# RGB-Controller.net
KiCad netlist of a schematic drawn in EasyEDA
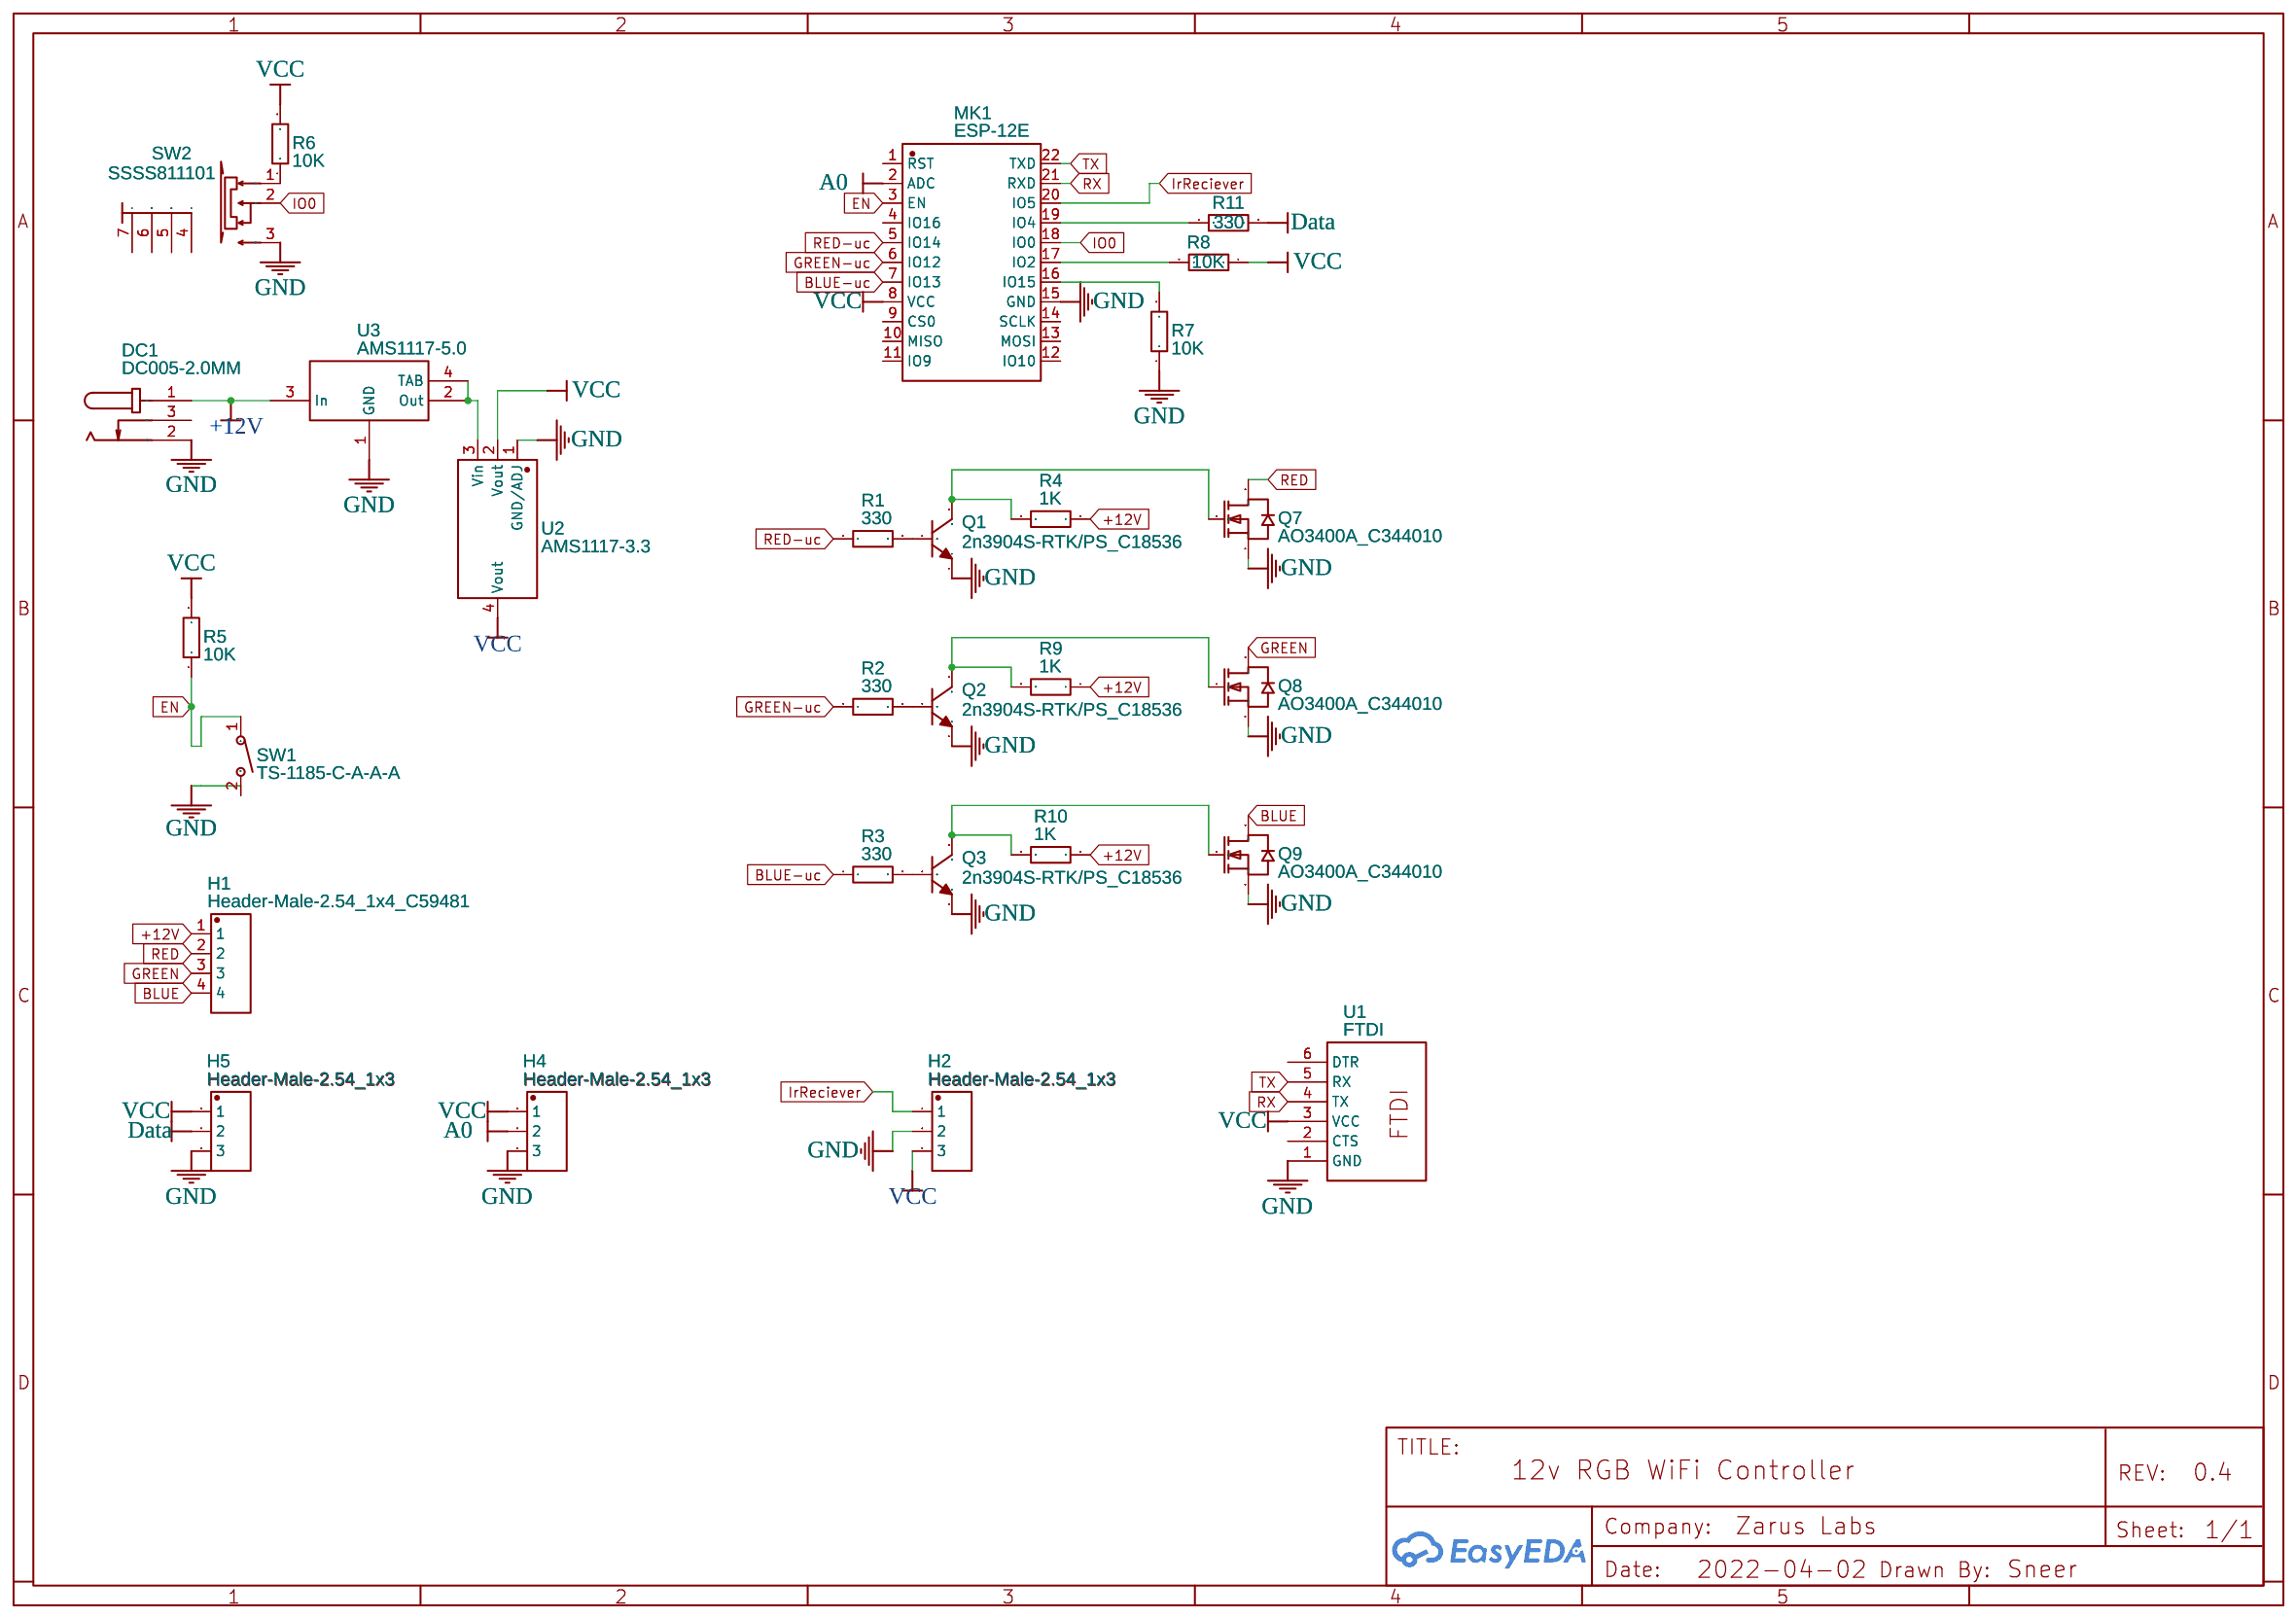
[diagram p0: schematic sheet]

(export (version "E")
  (design (tool "Eeschema 10.0.6"))
  (components
    (comp (ref "DC1")
      (value "DC005-2.0MM")
      (fields (field (name "BOM_Supplier Part") "C111567"))
      (libsource (lib "") (part "DC005-2.0MM"))
    )
    (comp (ref "H1")
      (value "Header-Male-2.54_1x4_C59481")
      (fields
        (field (name "BOM_Manufacturer Part") "Headers  Pins 1*4P")
        (field (name "BOM_Supplier Part") "C59481")
      )
      (libsource (lib "") (part "Header-Male-2.54_1x4_C59481"))
    )
    (comp (ref "H2") (value "Header-Male-2.54_1x3") (libsource (lib "") (part "Header-Male-2.54_1x3")))
    (comp (ref "H4") (value "Header-Male-2.54_1x3") (libsource (lib "") (part "Header-Male-2.54_1x3")))
    (comp (ref "H5") (value "Header-Male-2.54_1x3") (libsource (lib "") (part "Header-Male-2.54_1x3")))
    (comp (ref "MK1")
      (value "ESP-12E")
      (fields (field (name "BOM_Supplier Part") "C89297"))
      (libsource (lib "") (part "ESP-12E"))
    )
    (comp (ref "Q1")
      (value "2n3904S-RTK/PS_C18536")
      (fields
        (field (name "BOM_Manufacturer Part") "2n3904S-RTK/PS")
        (field (name "BOM_Supplier Part") "C18536")
      )
      (libsource (lib "") (part "2n3904S-RTK/PS_C18536"))
    )
    (comp (ref "Q2")
      (value "2n3904S-RTK/PS_C18536")
      (fields
        (field (name "BOM_Manufacturer Part") "2n3904S-RTK/PS")
        (field (name "BOM_Supplier Part") "C18536")
      )
      (libsource (lib "") (part "2n3904S-RTK/PS_C18536"))
    )
    (comp (ref "Q3")
      (value "2n3904S-RTK/PS_C18536")
      (fields
        (field (name "BOM_Manufacturer Part") "2n3904S-RTK/PS")
        (field (name "BOM_Supplier Part") "C18536")
      )
      (libsource (lib "") (part "2n3904S-RTK/PS_C18536"))
    )
    (comp (ref "Q7")
      (value "AO3400A_C344010")
      (fields (field (name "BOM_Manufacturer Part") "AO3400A") (field (name "BOM_Supplier Part") "C344010"))
      (libsource (lib "") (part "AO3400A_C344010"))
    )
    (comp (ref "Q8")
      (value "AO3400A_C344010")
      (fields (field (name "BOM_Manufacturer Part") "AO3400A") (field (name "BOM_Supplier Part") "C344010"))
      (libsource (lib "") (part "AO3400A_C344010"))
    )
    (comp (ref "Q9")
      (value "AO3400A_C344010")
      (fields (field (name "BOM_Manufacturer Part") "AO3400A") (field (name "BOM_Supplier Part") "C344010"))
      (libsource (lib "") (part "AO3400A_C344010"))
    )
    (comp (ref "R1")
      (value "330")
      (fields
        (field (name "BOM_Manufacturer Part") "0805W8J0331T5E")
        (field (name "BOM_Supplier Part") "C25306")
      )
      (libsource (lib "") (part "0805W8J0331T5E"))
    )
    (comp (ref "R2")
      (value "330")
      (fields
        (field (name "BOM_Manufacturer Part") "0805W8J0331T5E")
        (field (name "BOM_Supplier Part") "C25306")
      )
      (libsource (lib "") (part "0805W8J0331T5E"))
    )
    (comp (ref "R3")
      (value "330")
      (fields
        (field (name "BOM_Manufacturer Part") "0805W8J0331T5E")
        (field (name "BOM_Supplier Part") "C25306")
      )
      (libsource (lib "") (part "0805W8J0331T5E"))
    )
    (comp (ref "R4")
      (value "1K")
      (fields
        (field (name "BOM_Manufacturer Part") "1210W3J0102T5E")
        (field (name "BOM_Supplier Part") "C25681")
      )
      (libsource (lib "") (part "1210W3J0102T5E"))
    )
    (comp (ref "R5")
      (value "10K")
      (fields
        (field (name "BOM_Manufacturer Part") "1206W4F1002T5E")
        (field (name "BOM_Supplier Part") "C17902")
      )
      (libsource (lib "") (part "1206W4F1002T5E"))
    )
    (comp (ref "R6")
      (value "10K")
      (fields
        (field (name "BOM_Manufacturer Part") "1206W4F1002T5E")
        (field (name "BOM_Supplier Part") "C17902")
      )
      (libsource (lib "") (part "1206W4F1002T5E"))
    )
    (comp (ref "R7")
      (value "10K")
      (fields
        (field (name "BOM_Manufacturer Part") "1206W4F1002T5E")
        (field (name "BOM_Supplier Part") "C17902")
      )
      (libsource (lib "") (part "1206W4F1002T5E"))
    )
    (comp (ref "R8")
      (value "10K")
      (fields
        (field (name "BOM_Manufacturer Part") "1206W4F1002T5E")
        (field (name "BOM_Supplier Part") "C17902")
      )
      (libsource (lib "") (part "1206W4F1002T5E_1"))
    )
    (comp (ref "R9")
      (value "1K")
      (fields
        (field (name "BOM_Manufacturer Part") "1210W3J0102T5E")
        (field (name "BOM_Supplier Part") "C25681")
      )
      (libsource (lib "") (part "1210W3J0102T5E"))
    )
    (comp (ref "R10")
      (value "1K")
      (fields
        (field (name "BOM_Manufacturer Part") "1210W3J0102T5E")
        (field (name "BOM_Supplier Part") "C25681")
      )
      (libsource (lib "") (part "1210W3J0102T5E"))
    )
    (comp (ref "R11")
      (value "330")
      (fields
        (field (name "BOM_Manufacturer Part") "0805W8J0331T5E")
        (field (name "BOM_Supplier Part") "C25306")
      )
      (libsource (lib "") (part "0805W8J0331T5E"))
    )
    (comp (ref "SW1")
      (value "TS-1185-C-A-A-A")
      (fields (field (name "BOM_Supplier Part") "C561518"))
      (libsource (lib "") (part "TS-1185-C-A-A-A"))
    )
    (comp (ref "SW2")
      (value "SSSS811101")
      (fields (field (name "BOM_Supplier Part") "C109335"))
      (libsource (lib "") (part "SSSS811101"))
    )
    (comp (ref "U1") (value "FTDI") (libsource (lib "") (part "FTDI")))
    (comp (ref "U2")
      (value "AMS1117-3.3")
      (fields (field (name "BOM_Supplier Part") "C6186"))
      (libsource (lib "") (part "AMS1117-3.3"))
    )
    (comp (ref "U3")
      (value "AMS1117-5.0")
      (fields (field (name "BOM_Supplier Part") "C6187"))
      (libsource (lib "") (part "AMS1117-5.0"))
    )
  )
  (nets
    (net (code "1") (name "+12V") (class "Default")
      (node (ref "DC1") (pin "1") (pinfunction "1_1") (pintype "unspecified"))
      (node (ref "H1") (pin "1") (pinfunction "1_1") (pintype "unspecified"))
      (node (ref "R10") (pin "1") (pinfunction "1_1") (pintype "input"))
      (node (ref "R4") (pin "1") (pinfunction "1_1") (pintype "input"))
      (node (ref "R9") (pin "1") (pinfunction "1_1") (pintype "input"))
      (node (ref "U3") (pin "3") (pinfunction "In_3") (pintype "unspecified"))
    )
    (net (code "2") (name "A0") (class "Default")
      (node (ref "H4") (pin "2") (pinfunction "2_2") (pintype "unspecified"))
      (node (ref "MK1") (pin "2") (pinfunction "ADC_2") (pintype "unspecified"))
    )
    (net (code "3") (name "BLUE") (class "Default")
      (node (ref "H1") (pin "4") (pinfunction "4_4") (pintype "unspecified"))
      (node (ref "Q9") (pin "3") (pinfunction "D_3") (pintype "unspecified"))
    )
    (net (code "4") (name "BLUE-uc") (class "Default")
      (node (ref "MK1") (pin "7") (pinfunction "IO13_7") (pintype "unspecified"))
      (node (ref "R3") (pin "1") (pinfunction "1_1") (pintype "input"))
    )
    (net (code "5") (name "Data") (class "Default")
      (node (ref "H5") (pin "2") (pinfunction "2_2") (pintype "unspecified"))
      (node (ref "R11") (pin "2") (pinfunction "2_2") (pintype "input"))
    )
    (net (code "6") (name "EN") (class "Default")
      (node (ref "MK1") (pin "3") (pinfunction "EN_3") (pintype "unspecified"))
      (node (ref "R5") (pin "1") (pinfunction "1_1") (pintype "input"))
      (node (ref "SW1") (pin "1") (pinfunction "1_1") (pintype "unspecified"))
    )
    (net (code "7") (name "GND") (class "Default")
      (node (ref "DC1") (pin "2") (pinfunction "2_2") (pintype "unspecified"))
      (node (ref "H2") (pin "2") (pinfunction "2_2") (pintype "unspecified"))
      (node (ref "H4") (pin "3") (pinfunction "3_3") (pintype "unspecified"))
      (node (ref "H5") (pin "3") (pinfunction "3_3") (pintype "unspecified"))
      (node (ref "MK1") (pin "15") (pinfunction "GND_15") (pintype "unspecified"))
      (node (ref "Q1") (pin "1") (pinfunction "E_1") (pintype "input"))
      (node (ref "Q2") (pin "1") (pinfunction "E_1") (pintype "input"))
      (node (ref "Q3") (pin "1") (pinfunction "E_1") (pintype "input"))
      (node (ref "Q7") (pin "2") (pinfunction "S_2") (pintype "unspecified"))
      (node (ref "Q8") (pin "2") (pinfunction "S_2") (pintype "unspecified"))
      (node (ref "Q9") (pin "2") (pinfunction "S_2") (pintype "unspecified"))
      (node (ref "R7") (pin "1") (pinfunction "1_1") (pintype "input"))
      (node (ref "SW1") (pin "2") (pinfunction "2_2") (pintype "unspecified"))
      (node (ref "SW2") (pin "3") (pinfunction "3_3") (pintype "unspecified"))
      (node (ref "U1") (pin "1") (pinfunction "GND_1") (pintype "unspecified"))
      (node (ref "U2") (pin "1") (pinfunction "GND/ADJ_1") (pintype "unspecified"))
      (node (ref "U3") (pin "1") (pinfunction "GND_1") (pintype "unspecified"))
    )
    (net (code "8") (name "GREEN") (class "Default")
      (node (ref "H1") (pin "3") (pinfunction "3_3") (pintype "unspecified"))
      (node (ref "Q8") (pin "3") (pinfunction "D_3") (pintype "unspecified"))
    )
    (net (code "9") (name "GREEN-uc") (class "Default")
      (node (ref "MK1") (pin "6") (pinfunction "IO12_6") (pintype "unspecified"))
      (node (ref "R2") (pin "1") (pinfunction "1_1") (pintype "input"))
    )
    (net (code "10") (name "IO0") (class "Default")
      (node (ref "MK1") (pin "18") (pinfunction "IO0_18") (pintype "unspecified"))
      (node (ref "SW2") (pin "2") (pinfunction "2_2") (pintype "unspecified"))
    )
    (net (code "11") (name "IrReciever") (class "Default")
      (node (ref "H2") (pin "1") (pinfunction "1_1") (pintype "unspecified"))
      (node (ref "MK1") (pin "20") (pinfunction "IO5_20") (pintype "unspecified"))
    )
    (net (code "12") (name "Net-(MK1-IO2)") (class "Default")
      (node (ref "MK1") (pin "17") (pinfunction "IO2_17") (pintype "unspecified"))
      (node (ref "R8") (pin "2") (pinfunction "2_2") (pintype "input"))
    )
    (net (code "13") (name "Net-(MK1-IO4)") (class "Default")
      (node (ref "MK1") (pin "19") (pinfunction "IO4_19") (pintype "unspecified"))
      (node (ref "R11") (pin "1") (pinfunction "1_1") (pintype "input"))
    )
    (net (code "14") (name "Net-(MK1-IO15)") (class "Default")
      (node (ref "MK1") (pin "16") (pinfunction "IO15_16") (pintype "unspecified"))
      (node (ref "R7") (pin "2") (pinfunction "2_2") (pintype "input"))
    )
    (net (code "15") (name "Net-(Q1-B)") (class "Default")
      (node (ref "Q1") (pin "2") (pinfunction "B_2") (pintype "input"))
      (node (ref "R1") (pin "2") (pinfunction "2_2") (pintype "input"))
    )
    (net (code "16") (name "Net-(Q1-C)") (class "Default")
      (node (ref "Q1") (pin "3") (pinfunction "C_3") (pintype "input"))
      (node (ref "Q7") (pin "1") (pinfunction "G_1") (pintype "unspecified"))
      (node (ref "R4") (pin "2") (pinfunction "2_2") (pintype "input"))
    )
    (net (code "17") (name "Net-(Q2-B)") (class "Default")
      (node (ref "Q2") (pin "2") (pinfunction "B_2") (pintype "input"))
      (node (ref "R2") (pin "2") (pinfunction "2_2") (pintype "input"))
    )
    (net (code "18") (name "Net-(Q2-C)") (class "Default")
      (node (ref "Q2") (pin "3") (pinfunction "C_3") (pintype "input"))
      (node (ref "Q8") (pin "1") (pinfunction "G_1") (pintype "unspecified"))
      (node (ref "R9") (pin "2") (pinfunction "2_2") (pintype "input"))
    )
    (net (code "19") (name "Net-(Q3-B)") (class "Default")
      (node (ref "Q3") (pin "2") (pinfunction "B_2") (pintype "input"))
      (node (ref "R3") (pin "2") (pinfunction "2_2") (pintype "input"))
    )
    (net (code "20") (name "Net-(Q3-C)") (class "Default")
      (node (ref "Q3") (pin "3") (pinfunction "C_3") (pintype "input"))
      (node (ref "Q9") (pin "1") (pinfunction "G_1") (pintype "unspecified"))
      (node (ref "R10") (pin "2") (pinfunction "2_2") (pintype "input"))
    )
    (net (code "21") (name "Net-(R6-Pad1)") (class "Default")
      (node (ref "R6") (pin "1") (pinfunction "1_1") (pintype "input"))
      (node (ref "SW2") (pin "1") (pinfunction "1_1") (pintype "unspecified"))
    )
    (net (code "22") (name "Net-(U2-Vin)") (class "Default")
      (node (ref "U2") (pin "3") (pinfunction "Vin_3") (pintype "unspecified"))
      (node (ref "U3") (pin "2") (pinfunction "Out_2") (pintype "unspecified"))
      (node (ref "U3") (pin "4") (pinfunction "TAB_4") (pintype "unspecified"))
    )
    (net (code "23") (name "RED") (class "Default")
      (node (ref "H1") (pin "2") (pinfunction "2_2") (pintype "unspecified"))
      (node (ref "Q7") (pin "3") (pinfunction "D_3") (pintype "unspecified"))
    )
    (net (code "24") (name "RED-uc") (class "Default")
      (node (ref "MK1") (pin "5") (pinfunction "IO14_5") (pintype "unspecified"))
      (node (ref "R1") (pin "1") (pinfunction "1_1") (pintype "input"))
    )
    (net (code "25") (name "RX") (class "Default")
      (node (ref "MK1") (pin "21") (pinfunction "RXD_21") (pintype "unspecified"))
      (node (ref "U1") (pin "4") (pinfunction "TX_4") (pintype "unspecified"))
    )
    (net (code "26") (name "TX") (class "Default")
      (node (ref "MK1") (pin "22") (pinfunction "TXD_22") (pintype "unspecified"))
      (node (ref "U1") (pin "5") (pinfunction "RX_5") (pintype "unspecified"))
    )
    (net (code "27") (name "VCC") (class "Default")
      (node (ref "H2") (pin "3") (pinfunction "3_3") (pintype "unspecified"))
      (node (ref "H4") (pin "1") (pinfunction "1_1") (pintype "unspecified"))
      (node (ref "H5") (pin "1") (pinfunction "1_1") (pintype "unspecified"))
      (node (ref "MK1") (pin "8") (pinfunction "VCC_8") (pintype "unspecified"))
      (node (ref "R5") (pin "2") (pinfunction "2_2") (pintype "input"))
      (node (ref "R6") (pin "2") (pinfunction "2_2") (pintype "input"))
      (node (ref "R8") (pin "1") (pinfunction "1_1") (pintype "input"))
      (node (ref "U1") (pin "3") (pinfunction "VCC_3") (pintype "unspecified"))
      (node (ref "U2") (pin "2") (pinfunction "Vout_2") (pintype "unspecified"))
      (node (ref "U2") (pin "4") (pinfunction "Vout_4") (pintype "unspecified"))
    )
    (net (code "28") (name "unconnected-(DC1-Pad3)") (class "Default")
      (node (ref "DC1") (pin "3") (pinfunction "3_3") (pintype "unspecified"))
    )
    (net (code "29") (name "unconnected-(MK1-CS0-Pad9)") (class "Default")
      (node (ref "MK1") (pin "9") (pinfunction "CS0_9") (pintype "unspecified"))
    )
    (net (code "30") (name "unconnected-(MK1-IO9-Pad11)") (class "Default")
      (node (ref "MK1") (pin "11") (pinfunction "IO9_11") (pintype "unspecified"))
    )
    (net (code "31") (name "unconnected-(MK1-IO10-Pad12)") (class "Default")
      (node (ref "MK1") (pin "12") (pinfunction "IO10_12") (pintype "unspecified"))
    )
    (net (code "32") (name "unconnected-(MK1-IO16-Pad4)") (class "Default")
      (node (ref "MK1") (pin "4") (pinfunction "IO16_4") (pintype "unspecified"))
    )
    (net (code "33") (name "unconnected-(MK1-MISO-Pad10)") (class "Default")
      (node (ref "MK1") (pin "10") (pinfunction "MISO_10") (pintype "unspecified"))
    )
    (net (code "34") (name "unconnected-(MK1-MOSI-Pad13)") (class "Default")
      (node (ref "MK1") (pin "13") (pinfunction "MOSI_13") (pintype "unspecified"))
    )
    (net (code "35") (name "unconnected-(MK1-RST-Pad1)") (class "Default")
      (node (ref "MK1") (pin "1") (pinfunction "RST_1") (pintype "unspecified"))
    )
    (net (code "36") (name "unconnected-(MK1-SCLK-Pad14)") (class "Default")
      (node (ref "MK1") (pin "14") (pinfunction "SCLK_14") (pintype "unspecified"))
    )
    (net (code "37") (name "unconnected-(SW2-Pad4)") (class "Default")
      (node (ref "SW2") (pin "4") (pinfunction "4_4") (pintype "unspecified"))
    )
    (net (code "38") (name "unconnected-(SW2-Pad5)") (class "Default")
      (node (ref "SW2") (pin "5") (pinfunction "5_5") (pintype "unspecified"))
    )
    (net (code "39") (name "unconnected-(SW2-Pad6)") (class "Default")
      (node (ref "SW2") (pin "6") (pinfunction "6_6") (pintype "unspecified"))
    )
    (net (code "40") (name "unconnected-(SW2-Pad7)") (class "Default")
      (node (ref "SW2") (pin "7") (pinfunction "7_7") (pintype "unspecified"))
    )
    (net (code "41") (name "unconnected-(U1-CTS-Pad2)") (class "Default")
      (node (ref "U1") (pin "2") (pinfunction "CTS_2") (pintype "unspecified"))
    )
    (net (code "42") (name "unconnected-(U1-DTR-Pad6)") (class "Default")
      (node (ref "U1") (pin "6") (pinfunction "DTR_6") (pintype "unspecified"))
    )
  )
)
